# Regulador_3_3V.net
KiCad netlist of a schematic drawn in Altium Designer
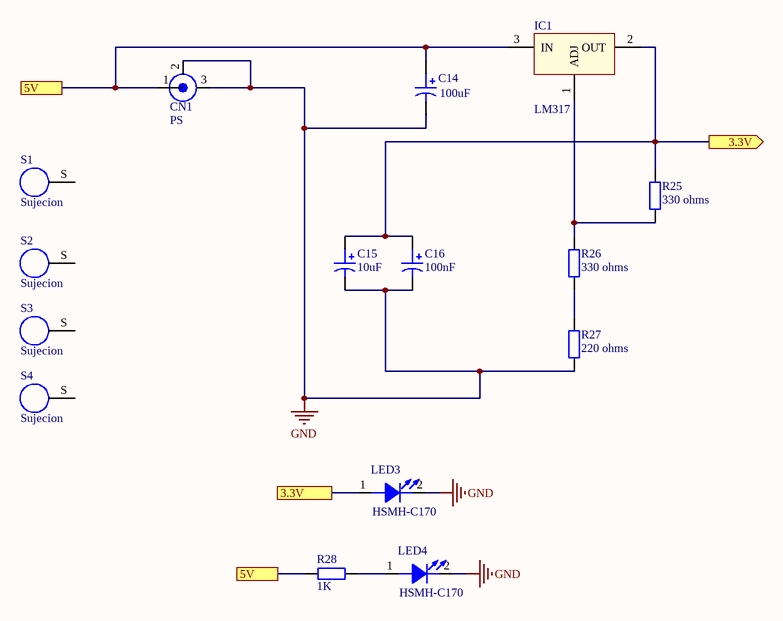
[diagram p0: Regulador_3.3V.SchDoc]

(export (version "E")
  (design (tool "Eeschema 10.0.6"))
  (components
    (comp (ref "C14")
      (value "100uF")
      (footprint "RADIAL C")
      (description "Polarized Capacitor")
      (fields (field (name "Comment") "Cap Pol") (field (name "PUBLISHER") "Altium Limited"))
      (libsource (lib "hphonglib") (part "Cap Pol"))
    )
    (comp (ref "C15")
      (value "10uF")
      (footprint "RADIAL C")
      (description "Polarized Capacitor")
      (fields (field (name "Comment") "Cap Pol") (field (name "PUBLISHER") "Altium Limited"))
      (libsource (lib "hphonglib") (part "Cap Pol"))
    )
    (comp (ref "C16")
      (value "100nF")
      (footprint "RADIAL C")
      (description "Polarized Capacitor")
      (fields (field (name "Comment") "Cap Pol") (field (name "PUBLISHER") "Altium Limited"))
      (libsource (lib "hphonglib") (part "Cap Pol"))
    )
    (comp (ref "CN1")
      (value "PS")
      (footprint "JACK DC")
      (description "DC Power Jack, 2.5mm, KLD Series, PCB Mount")
      (libsource (lib "hphonglib") (part "CON.DCjack"))
    )
    (comp (ref "IC1")
      (value "LM317")
      (footprint "QTO-220")
      (description "Adj Voltage +1.2 -> +37V")
      (libsource (lib "hphonglib") (part "LM317_1"))
    )
    (comp (ref "LED3")
      (value "HSMH-C170")
      (footprint "LED.SMD.WHITE")
      (description "Typical GaAs SMD LED")
      (fields (field (name "MANUFACTURER") "Lite-On Inc") (field (name "PUBLISHER") "Hoang Nguyen"))
      (libsource (lib "hphonglib") (part "LED_1"))
    )
    (comp (ref "LED4")
      (value "HSMH-C170")
      (footprint "LED.SMD.WHITE")
      (description "Typical GaAs SMD LED")
      (fields (field (name "MANUFACTURER") "Lite-On Inc") (field (name "PUBLISHER") "Hoang Nguyen"))
      (libsource (lib "hphonglib") (part "LED_1"))
    )
    (comp (ref "R25")
      (value "330 ohms")
      (footprint "SM-1206")
      (description "Resistor SMD")
      (libsource (lib "hphonglib") (part "RM"))
    )
    (comp (ref "R26")
      (value "330 ohms")
      (footprint "SM-1206")
      (description "Resistor SMD")
      (libsource (lib "hphonglib") (part "RM"))
    )
    (comp (ref "R27")
      (value "220 ohms")
      (footprint "SM-1206")
      (description "Resistor SMD")
      (libsource (lib "hphonglib") (part "RM"))
    )
    (comp (ref "R28")
      (value "1K")
      (footprint "SM-1206")
      (description "Resistor SMD")
      (libsource (lib "hphonglib") (part "RM"))
    )
    (comp (ref "S1")
      (value "Sujecion")
      (footprint "SUJECION")
      (libsource (lib "Schlib-ESP-01S-WS-V1.0") (part "SUJECION"))
    )
    (comp (ref "S2")
      (value "Sujecion")
      (footprint "SUJECION")
      (libsource (lib "Schlib-ESP-01S-WS-V1.0") (part "SUJECION"))
    )
    (comp (ref "S3")
      (value "Sujecion")
      (footprint "SUJECION")
      (libsource (lib "Schlib-ESP-01S-WS-V1.0") (part "SUJECION"))
    )
    (comp (ref "S4")
      (value "Sujecion")
      (footprint "SUJECION")
      (libsource (lib "Schlib-ESP-01S-WS-V1.0") (part "SUJECION"))
    )
  )
  (nets
    (net (code "1") (name "/3.3V") (class "Default")
      (node (ref "C15") (pin "1") (pinfunction "1_1") (pintype "passive"))
      (node (ref "C16") (pin "1") (pinfunction "1_1") (pintype "passive"))
      (node (ref "IC1") (pin "2") (pinfunction "OUT_2") (pintype "passive"))
      (node (ref "LED3") (pin "1") (pinfunction "A_1") (pintype "passive"))
      (node (ref "R25") (pin "2") (pinfunction "2_2") (pintype "passive"))
    )
    (net (code "2") (name "/5V") (class "Default")
      (node (ref "C14") (pin "1") (pinfunction "1_1") (pintype "passive"))
      (node (ref "CN1") (pin "1") (pinfunction "CENTER_1") (pintype "power_in"))
      (node (ref "IC1") (pin "3") (pinfunction "IN_3") (pintype "passive"))
      (node (ref "R28") (pin "1") (pinfunction "1_1") (pintype "passive"))
    )
    (net (code "3") (name "GND") (class "Default")
      (node (ref "C14") (pin "2") (pinfunction "2_2") (pintype "passive"))
      (node (ref "C15") (pin "2") (pinfunction "2_2") (pintype "passive"))
      (node (ref "C16") (pin "2") (pinfunction "2_2") (pintype "passive"))
      (node (ref "CN1") (pin "2") (pinfunction "SHIELD_2") (pintype "power_in"))
      (node (ref "CN1") (pin "3") (pinfunction "SHIELD_3") (pintype "passive"))
      (node (ref "LED3") (pin "2") (pinfunction "K_2") (pintype "passive"))
      (node (ref "LED4") (pin "2") (pinfunction "K_2") (pintype "passive"))
      (node (ref "R27") (pin "2") (pinfunction "2_2") (pintype "passive"))
    )
    (net (code "4") (name "Net-(IC1-ADJ)") (class "Default")
      (node (ref "IC1") (pin "1") (pinfunction "ADJ_1") (pintype "passive"))
      (node (ref "R25") (pin "1") (pinfunction "1_1") (pintype "passive"))
      (node (ref "R26") (pin "1") (pinfunction "1_1") (pintype "passive"))
    )
    (net (code "5") (name "Net-(LED4-A)") (class "Default")
      (node (ref "LED4") (pin "1") (pinfunction "A_1") (pintype "passive"))
      (node (ref "R28") (pin "2") (pinfunction "2_2") (pintype "passive"))
    )
    (net (code "6") (name "Net-(R26-Pad2)") (class "Default")
      (node (ref "R26") (pin "2") (pinfunction "2_2") (pintype "passive"))
      (node (ref "R27") (pin "1") (pinfunction "1_1") (pintype "passive"))
    )
    (net (code "7") (name "unconnected-(S1-PadS)") (class "Default")
      (node (ref "S1") (pin "S") (pinfunction "S_S") (pintype "passive"))
    )
    (net (code "8") (name "unconnected-(S2-PadS)") (class "Default")
      (node (ref "S2") (pin "S") (pinfunction "S_S") (pintype "passive"))
    )
    (net (code "9") (name "unconnected-(S3-PadS)") (class "Default")
      (node (ref "S3") (pin "S") (pinfunction "S_S") (pintype "passive"))
    )
    (net (code "10") (name "unconnected-(S4-PadS)") (class "Default")
      (node (ref "S4") (pin "S") (pinfunction "S_S") (pintype "passive"))
    )
  )
)
